# FMC_HPC_LPC_Signals.net
KiCad netlist of a schematic drawn in Altium Designer
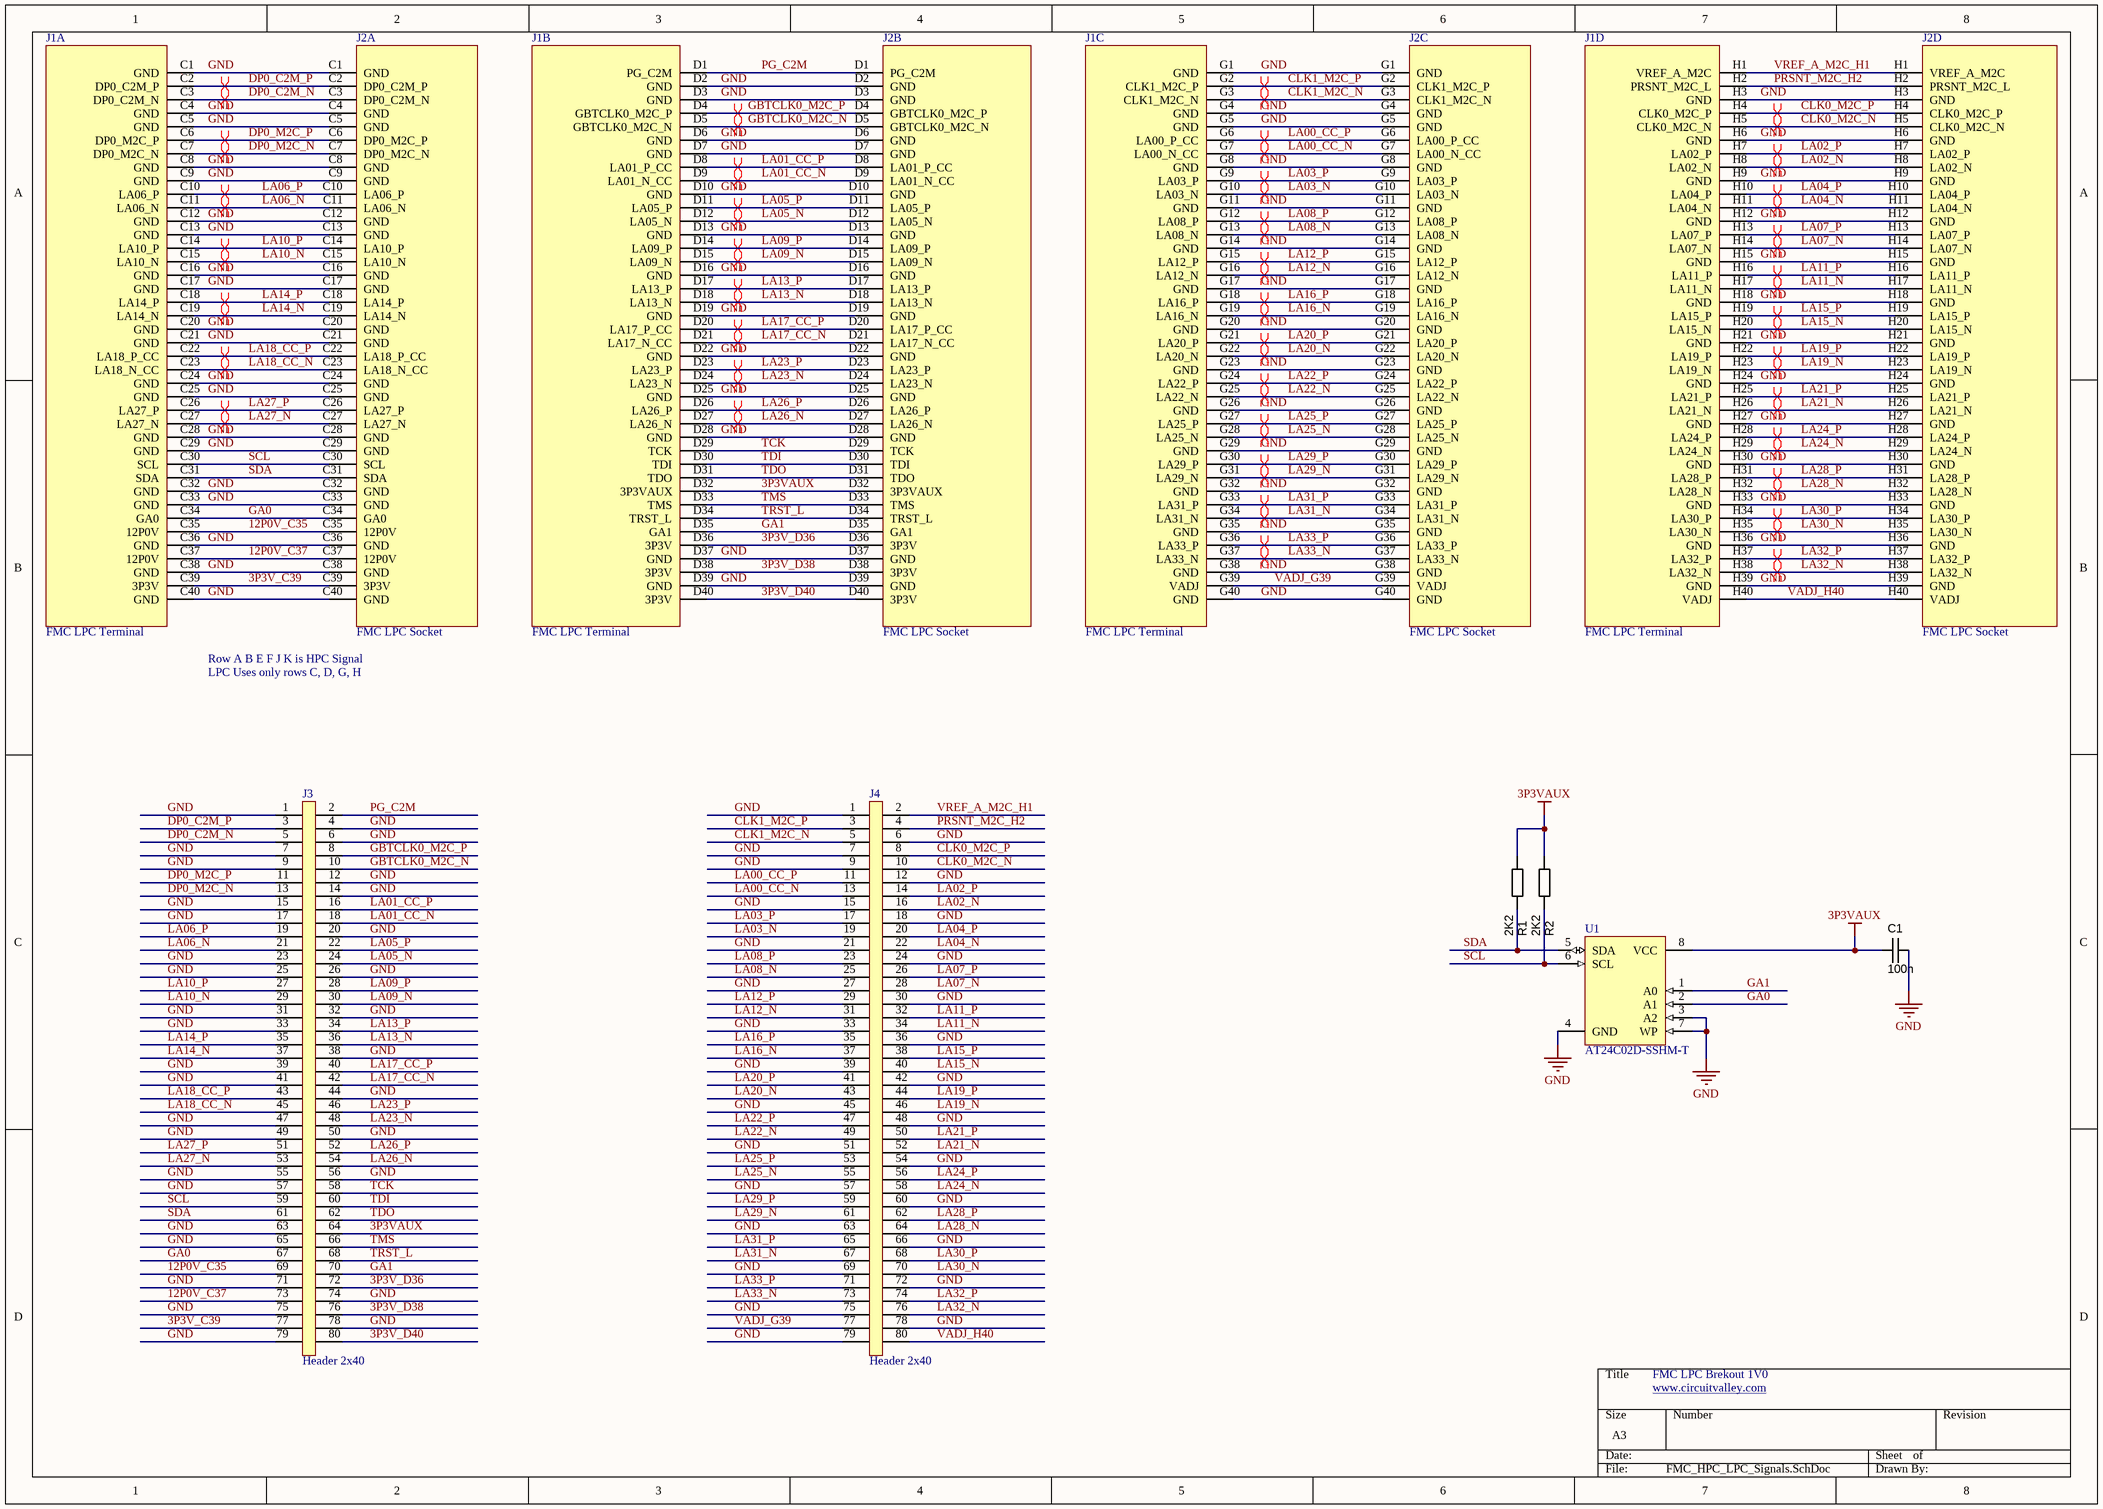
[diagram p0: FMC_HPC_LPC_Signals.SchDoc]

(export (version "E")
  (design (tool "Eeschema 10.0.6"))
  (components
    (comp (ref "C1")
      (value "100n")
      (footprint "CAPC1005N")
      (description "Capacitor SMD Cer 10nF 10% 16V X7R 0402")
      (fields (field (name "TOLERANCE") "±10%"))
      (libsource (lib "PBL - Capacitors") (part "CAPC_10n_0402_16V_10%"))
    )
    (comp (ref "J1")
      (value "FMC LPC Terminal")
      (footprint "SAMTEC_ASP-134604-01")
      (description "FMC LPC Connector Terminal ASP-134604-01")
      (libsource (lib "cvlib") (part "FMC_LPC_TERMINAL"))
    )
    (comp (ref "J2")
      (value "FMC LPC Socket")
      (footprint "SAMTEC_ASP-134603-01")
      (description "FMC LPC Connector Socket  ASP-134603-01")
      (libsource (lib "cvlib") (part "FMC_LPC_SOCKET"))
    )
    (comp (ref "J3")
      (value "Header 2x40")
      (footprint "FTSH-140-01-L-DV")
      (libsource (lib "cvlib") (part "Header_2x40"))
    )
    (comp (ref "J4")
      (value "Header 2x40")
      (footprint "FTSH-140-01-L-DV")
      (libsource (lib "cvlib") (part "Header_2x40"))
    )
    (comp (ref "R1")
      (value "2K2")
      (footprint "RESC1005N")
      (description "Resistor SMD chip 3.3k Ohm 0.063W 5% 0402")
      (fields (field (name "TOLERANCE") "±5%") (field (name "Comment") "Thick Film"))
      (libsource (lib "PBL - Resistors") (part "RES_3K3_0402_5%"))
    )
    (comp (ref "R2")
      (value "2K2")
      (footprint "RESC1005N")
      (description "Resistor SMD chip 3.3k Ohm 0.063W 5% 0402")
      (fields (field (name "TOLERANCE") "±5%") (field (name "Comment") "Thick Film"))
      (libsource (lib "PBL - Resistors") (part "RES_3K3_0402_5%"))
    )
    (comp (ref "U1")
      (value "AT24C02D-SSHM-T")
      (footprint "SOIC8")
      (description "2Kbit I2C EEPROM")
      (libsource (lib "cvlib") (part "AT24C02D-SSHM-T"))
    )
  )
  (nets
    (net (code "1") (name "/3P3V_C39") (class "Default")
      (node (ref "J1") (pin "C39") (pinfunction "3P3V_C39") (pintype "passive"))
      (node (ref "J2") (pin "C39") (pinfunction "3P3V_C39") (pintype "passive"))
      (node (ref "J3") (pin "77") (pinfunction "77_77") (pintype "passive"))
    )
    (net (code "2") (name "/3P3V_D36") (class "Default")
      (node (ref "J1") (pin "D36") (pinfunction "3P3V_D36") (pintype "passive"))
      (node (ref "J2") (pin "D36") (pinfunction "3P3V_D36") (pintype "passive"))
      (node (ref "J3") (pin "72") (pinfunction "72_72") (pintype "passive"))
    )
    (net (code "3") (name "/3P3V_D38") (class "Default")
      (node (ref "J1") (pin "D38") (pinfunction "3P3V_D38") (pintype "passive"))
      (node (ref "J2") (pin "D38") (pinfunction "3P3V_D38") (pintype "passive"))
      (node (ref "J3") (pin "76") (pinfunction "76_76") (pintype "passive"))
    )
    (net (code "4") (name "/3P3V_D40") (class "Default")
      (node (ref "J1") (pin "D40") (pinfunction "3P3V_D40") (pintype "passive"))
      (node (ref "J2") (pin "D40") (pinfunction "3P3V_D40") (pintype "passive"))
      (node (ref "J3") (pin "80") (pinfunction "80_80") (pintype "passive"))
    )
    (net (code "5") (name "/12P0V_C35") (class "Default")
      (node (ref "J1") (pin "C35") (pinfunction "12P0V_C35") (pintype "passive"))
      (node (ref "J2") (pin "C35") (pinfunction "12P0V_C35") (pintype "passive"))
      (node (ref "J3") (pin "69") (pinfunction "69_69") (pintype "passive"))
    )
    (net (code "6") (name "/12P0V_C37") (class "Default")
      (node (ref "J1") (pin "C37") (pinfunction "12P0V_C37") (pintype "passive"))
      (node (ref "J2") (pin "C37") (pinfunction "12P0V_C37") (pintype "passive"))
      (node (ref "J3") (pin "73") (pinfunction "73_73") (pintype "passive"))
    )
    (net (code "7") (name "/CLK0_M2C_N") (class "Default")
      (node (ref "J1") (pin "H5") (pinfunction "CLK0_M2C_N_H5") (pintype "passive"))
      (node (ref "J2") (pin "H5") (pinfunction "CLK0_M2C_N_H5") (pintype "passive"))
      (node (ref "J4") (pin "10") (pinfunction "10_10") (pintype "passive"))
    )
    (net (code "8") (name "/CLK0_M2C_P") (class "Default")
      (node (ref "J1") (pin "H4") (pinfunction "CLK0_M2C_P_H4") (pintype "passive"))
      (node (ref "J2") (pin "H4") (pinfunction "CLK0_M2C_P_H4") (pintype "passive"))
      (node (ref "J4") (pin "8") (pinfunction "8_8") (pintype "passive"))
    )
    (net (code "9") (name "/CLK1_M2C_N") (class "Default")
      (node (ref "J1") (pin "G3") (pinfunction "CLK1_M2C_N_G3") (pintype "passive"))
      (node (ref "J2") (pin "G3") (pinfunction "CLK1_M2C_N_G3") (pintype "passive"))
      (node (ref "J4") (pin "5") (pinfunction "5_5") (pintype "passive"))
    )
    (net (code "10") (name "/CLK1_M2C_P") (class "Default")
      (node (ref "J1") (pin "G2") (pinfunction "CLK1_M2C_P_G2") (pintype "passive"))
      (node (ref "J2") (pin "G2") (pinfunction "CLK1_M2C_P_G2") (pintype "passive"))
      (node (ref "J4") (pin "3") (pinfunction "3_3") (pintype "passive"))
    )
    (net (code "11") (name "/DP0_C2M_N") (class "Default")
      (node (ref "J1") (pin "C3") (pinfunction "DP0_C2M_N_C3") (pintype "passive"))
      (node (ref "J2") (pin "C3") (pinfunction "DP0_C2M_N_C3") (pintype "passive"))
      (node (ref "J3") (pin "5") (pinfunction "5_5") (pintype "passive"))
    )
    (net (code "12") (name "/DP0_C2M_P") (class "Default")
      (node (ref "J1") (pin "C2") (pinfunction "DP0_C2M_P_C2") (pintype "passive"))
      (node (ref "J2") (pin "C2") (pinfunction "DP0_C2M_P_C2") (pintype "passive"))
      (node (ref "J3") (pin "3") (pinfunction "3_3") (pintype "passive"))
    )
    (net (code "13") (name "/DP0_M2C_N") (class "Default")
      (node (ref "J1") (pin "C7") (pinfunction "DP0_M2C_N_C7") (pintype "passive"))
      (node (ref "J2") (pin "C7") (pinfunction "DP0_M2C_N_C7") (pintype "passive"))
      (node (ref "J3") (pin "13") (pinfunction "13_13") (pintype "passive"))
    )
    (net (code "14") (name "/DP0_M2C_P") (class "Default")
      (node (ref "J1") (pin "C6") (pinfunction "DP0_M2C_P_C6") (pintype "passive"))
      (node (ref "J2") (pin "C6") (pinfunction "DP0_M2C_P_C6") (pintype "passive"))
      (node (ref "J3") (pin "11") (pinfunction "11_11") (pintype "passive"))
    )
    (net (code "15") (name "/GA0") (class "Default")
      (node (ref "J1") (pin "C34") (pinfunction "GA0_C34") (pintype "passive"))
      (node (ref "J2") (pin "C34") (pinfunction "GA0_C34") (pintype "passive"))
      (node (ref "J3") (pin "67") (pinfunction "67_67") (pintype "passive"))
      (node (ref "U1") (pin "2") (pinfunction "A1_2") (pintype "input"))
    )
    (net (code "16") (name "/GA1") (class "Default")
      (node (ref "J1") (pin "D35") (pinfunction "GA1_D35") (pintype "passive"))
      (node (ref "J2") (pin "D35") (pinfunction "GA1_D35") (pintype "passive"))
      (node (ref "J3") (pin "70") (pinfunction "70_70") (pintype "passive"))
      (node (ref "U1") (pin "1") (pinfunction "A0_1") (pintype "input"))
    )
    (net (code "17") (name "/GBTCLK0_M2C_N") (class "Default")
      (node (ref "J1") (pin "D5") (pinfunction "GBTCLK0_M2C_N_D5") (pintype "passive"))
      (node (ref "J2") (pin "D5") (pinfunction "GBTCLK0_M2C_N_D5") (pintype "passive"))
      (node (ref "J3") (pin "10") (pinfunction "10_10") (pintype "passive"))
    )
    (net (code "18") (name "/GBTCLK0_M2C_P") (class "Default")
      (node (ref "J1") (pin "D4") (pinfunction "GBTCLK0_M2C_P_D4") (pintype "passive"))
      (node (ref "J2") (pin "D4") (pinfunction "GBTCLK0_M2C_P_D4") (pintype "passive"))
      (node (ref "J3") (pin "8") (pinfunction "8_8") (pintype "passive"))
    )
    (net (code "19") (name "/LA00_CC_N") (class "Default")
      (node (ref "J1") (pin "G7") (pinfunction "LA00_N_CC_G7") (pintype "passive"))
      (node (ref "J2") (pin "G7") (pinfunction "LA00_N_CC_G7") (pintype "passive"))
      (node (ref "J4") (pin "13") (pinfunction "13_13") (pintype "passive"))
    )
    (net (code "20") (name "/LA00_CC_P") (class "Default")
      (node (ref "J1") (pin "G6") (pinfunction "LA00_P_CC_G6") (pintype "passive"))
      (node (ref "J2") (pin "G6") (pinfunction "LA00_P_CC_G6") (pintype "passive"))
      (node (ref "J4") (pin "11") (pinfunction "11_11") (pintype "passive"))
    )
    (net (code "21") (name "/LA01_CC_N") (class "Default")
      (node (ref "J1") (pin "D9") (pinfunction "LA01_N_CC_D9") (pintype "passive"))
      (node (ref "J2") (pin "D9") (pinfunction "LA01_N_CC_D9") (pintype "passive"))
      (node (ref "J3") (pin "18") (pinfunction "18_18") (pintype "passive"))
    )
    (net (code "22") (name "/LA01_CC_P") (class "Default")
      (node (ref "J1") (pin "D8") (pinfunction "LA01_P_CC_D8") (pintype "passive"))
      (node (ref "J2") (pin "D8") (pinfunction "LA01_P_CC_D8") (pintype "passive"))
      (node (ref "J3") (pin "16") (pinfunction "16_16") (pintype "passive"))
    )
    (net (code "23") (name "/LA02_N") (class "Default")
      (node (ref "J1") (pin "H8") (pinfunction "LA02_N_H8") (pintype "passive"))
      (node (ref "J2") (pin "H8") (pinfunction "LA02_N_H8") (pintype "passive"))
      (node (ref "J4") (pin "16") (pinfunction "16_16") (pintype "passive"))
    )
    (net (code "24") (name "/LA02_P") (class "Default")
      (node (ref "J1") (pin "H7") (pinfunction "LA02_P_H7") (pintype "passive"))
      (node (ref "J2") (pin "H7") (pinfunction "LA02_P_H7") (pintype "passive"))
      (node (ref "J4") (pin "14") (pinfunction "14_14") (pintype "passive"))
    )
    (net (code "25") (name "/LA03_N") (class "Default")
      (node (ref "J1") (pin "G10") (pinfunction "LA03_N_G10") (pintype "passive"))
      (node (ref "J2") (pin "G10") (pinfunction "LA03_N_G10") (pintype "passive"))
      (node (ref "J4") (pin "19") (pinfunction "19_19") (pintype "passive"))
    )
    (net (code "26") (name "/LA03_P") (class "Default")
      (node (ref "J1") (pin "G9") (pinfunction "LA03_P_G9") (pintype "passive"))
      (node (ref "J2") (pin "G9") (pinfunction "LA03_P_G9") (pintype "passive"))
      (node (ref "J4") (pin "17") (pinfunction "17_17") (pintype "passive"))
    )
    (net (code "27") (name "/LA04_N") (class "Default")
      (node (ref "J1") (pin "H11") (pinfunction "LA04_N_H11") (pintype "passive"))
      (node (ref "J2") (pin "H11") (pinfunction "LA04_N_H11") (pintype "passive"))
      (node (ref "J4") (pin "22") (pinfunction "22_22") (pintype "passive"))
    )
    (net (code "28") (name "/LA04_P") (class "Default")
      (node (ref "J1") (pin "H10") (pinfunction "LA04_P_H10") (pintype "passive"))
      (node (ref "J2") (pin "H10") (pinfunction "LA04_P_H10") (pintype "passive"))
      (node (ref "J4") (pin "20") (pinfunction "20_20") (pintype "passive"))
    )
    (net (code "29") (name "/LA05_N") (class "Default")
      (node (ref "J1") (pin "D12") (pinfunction "LA05_N_D12") (pintype "passive"))
      (node (ref "J2") (pin "D12") (pinfunction "LA05_N_D12") (pintype "passive"))
      (node (ref "J3") (pin "24") (pinfunction "24_24") (pintype "passive"))
    )
    (net (code "30") (name "/LA05_P") (class "Default")
      (node (ref "J1") (pin "D11") (pinfunction "LA05_P_D11") (pintype "passive"))
      (node (ref "J2") (pin "D11") (pinfunction "LA05_P_D11") (pintype "passive"))
      (node (ref "J3") (pin "22") (pinfunction "22_22") (pintype "passive"))
    )
    (net (code "31") (name "/LA06_N") (class "Default")
      (node (ref "J1") (pin "C11") (pinfunction "LA06_N_C11") (pintype "passive"))
      (node (ref "J2") (pin "C11") (pinfunction "LA06_N_C11") (pintype "passive"))
      (node (ref "J3") (pin "21") (pinfunction "21_21") (pintype "passive"))
    )
    (net (code "32") (name "/LA06_P") (class "Default")
      (node (ref "J1") (pin "C10") (pinfunction "LA06_P_C10") (pintype "passive"))
      (node (ref "J2") (pin "C10") (pinfunction "LA06_P_C10") (pintype "passive"))
      (node (ref "J3") (pin "19") (pinfunction "19_19") (pintype "passive"))
    )
    (net (code "33") (name "/LA07_N") (class "Default")
      (node (ref "J1") (pin "H14") (pinfunction "LA07_N_H14") (pintype "passive"))
      (node (ref "J2") (pin "H14") (pinfunction "LA07_N_H14") (pintype "passive"))
      (node (ref "J4") (pin "28") (pinfunction "28_28") (pintype "passive"))
    )
    (net (code "34") (name "/LA07_P") (class "Default")
      (node (ref "J1") (pin "H13") (pinfunction "LA07_P_H13") (pintype "passive"))
      (node (ref "J2") (pin "H13") (pinfunction "LA07_P_H13") (pintype "passive"))
      (node (ref "J4") (pin "26") (pinfunction "26_26") (pintype "passive"))
    )
    (net (code "35") (name "/LA08_N") (class "Default")
      (node (ref "J1") (pin "G13") (pinfunction "LA08_N_G13") (pintype "passive"))
      (node (ref "J2") (pin "G13") (pinfunction "LA08_N_G13") (pintype "passive"))
      (node (ref "J4") (pin "25") (pinfunction "25_25") (pintype "passive"))
    )
    (net (code "36") (name "/LA08_P") (class "Default")
      (node (ref "J1") (pin "G12") (pinfunction "LA08_P_G12") (pintype "passive"))
      (node (ref "J2") (pin "G12") (pinfunction "LA08_P_G12") (pintype "passive"))
      (node (ref "J4") (pin "23") (pinfunction "23_23") (pintype "passive"))
    )
    (net (code "37") (name "/LA09_N") (class "Default")
      (node (ref "J1") (pin "D15") (pinfunction "LA09_N_D15") (pintype "passive"))
      (node (ref "J2") (pin "D15") (pinfunction "LA09_N_D15") (pintype "passive"))
      (node (ref "J3") (pin "30") (pinfunction "30_30") (pintype "passive"))
    )
    (net (code "38") (name "/LA09_P") (class "Default")
      (node (ref "J1") (pin "D14") (pinfunction "LA09_P_D14") (pintype "passive"))
      (node (ref "J2") (pin "D14") (pinfunction "LA09_P_D14") (pintype "passive"))
      (node (ref "J3") (pin "28") (pinfunction "28_28") (pintype "passive"))
    )
    (net (code "39") (name "/LA10_N") (class "Default")
      (node (ref "J1") (pin "C15") (pinfunction "LA10_N_C15") (pintype "passive"))
      (node (ref "J2") (pin "C15") (pinfunction "LA10_N_C15") (pintype "passive"))
      (node (ref "J3") (pin "29") (pinfunction "29_29") (pintype "passive"))
    )
    (net (code "40") (name "/LA10_P") (class "Default")
      (node (ref "J1") (pin "C14") (pinfunction "LA10_P_C14") (pintype "passive"))
      (node (ref "J2") (pin "C14") (pinfunction "LA10_P_C14") (pintype "passive"))
      (node (ref "J3") (pin "27") (pinfunction "27_27") (pintype "passive"))
    )
    (net (code "41") (name "/LA11_N") (class "Default")
      (node (ref "J1") (pin "H17") (pinfunction "LA11_N_H17") (pintype "passive"))
      (node (ref "J2") (pin "H17") (pinfunction "LA11_N_H17") (pintype "passive"))
      (node (ref "J4") (pin "34") (pinfunction "34_34") (pintype "passive"))
    )
    (net (code "42") (name "/LA11_P") (class "Default")
      (node (ref "J1") (pin "H16") (pinfunction "LA11_P_H16") (pintype "passive"))
      (node (ref "J2") (pin "H16") (pinfunction "LA11_P_H16") (pintype "passive"))
      (node (ref "J4") (pin "32") (pinfunction "32_32") (pintype "passive"))
    )
    (net (code "43") (name "/LA12_N") (class "Default")
      (node (ref "J1") (pin "G16") (pinfunction "LA12_N_G16") (pintype "passive"))
      (node (ref "J2") (pin "G16") (pinfunction "LA12_N_G16") (pintype "passive"))
      (node (ref "J4") (pin "31") (pinfunction "31_31") (pintype "passive"))
    )
    (net (code "44") (name "/LA12_P") (class "Default")
      (node (ref "J1") (pin "G15") (pinfunction "LA12_P_G15") (pintype "passive"))
      (node (ref "J2") (pin "G15") (pinfunction "LA12_P_G15") (pintype "passive"))
      (node (ref "J4") (pin "29") (pinfunction "29_29") (pintype "passive"))
    )
    (net (code "45") (name "/LA13_N") (class "Default")
      (node (ref "J1") (pin "D18") (pinfunction "LA13_N_D18") (pintype "passive"))
      (node (ref "J2") (pin "D18") (pinfunction "LA13_N_D18") (pintype "passive"))
      (node (ref "J3") (pin "36") (pinfunction "36_36") (pintype "passive"))
    )
    (net (code "46") (name "/LA13_P") (class "Default")
      (node (ref "J1") (pin "D17") (pinfunction "LA13_P_D17") (pintype "passive"))
      (node (ref "J2") (pin "D17") (pinfunction "LA13_P_D17") (pintype "passive"))
      (node (ref "J3") (pin "34") (pinfunction "34_34") (pintype "passive"))
    )
    (net (code "47") (name "/LA14_N") (class "Default")
      (node (ref "J1") (pin "C19") (pinfunction "LA14_N_C19") (pintype "passive"))
      (node (ref "J2") (pin "C19") (pinfunction "LA14_N_C19") (pintype "passive"))
      (node (ref "J3") (pin "37") (pinfunction "37_37") (pintype "passive"))
    )
    (net (code "48") (name "/LA14_P") (class "Default")
      (node (ref "J1") (pin "C18") (pinfunction "LA14_P_C18") (pintype "passive"))
      (node (ref "J2") (pin "C18") (pinfunction "LA14_P_C18") (pintype "passive"))
      (node (ref "J3") (pin "35") (pinfunction "35_35") (pintype "passive"))
    )
    (net (code "49") (name "/LA15_N") (class "Default")
      (node (ref "J1") (pin "H20") (pinfunction "LA15_N_H20") (pintype "passive"))
      (node (ref "J2") (pin "H20") (pinfunction "LA15_N_H20") (pintype "passive"))
      (node (ref "J4") (pin "40") (pinfunction "40_40") (pintype "passive"))
    )
    (net (code "50") (name "/LA15_P") (class "Default")
      (node (ref "J1") (pin "H19") (pinfunction "LA15_P_H19") (pintype "passive"))
      (node (ref "J2") (pin "H19") (pinfunction "LA15_P_H19") (pintype "passive"))
      (node (ref "J4") (pin "38") (pinfunction "38_38") (pintype "passive"))
    )
    (net (code "51") (name "/LA16_N") (class "Default")
      (node (ref "J1") (pin "G19") (pinfunction "LA16_N_G19") (pintype "passive"))
      (node (ref "J2") (pin "G19") (pinfunction "LA16_N_G19") (pintype "passive"))
      (node (ref "J4") (pin "37") (pinfunction "37_37") (pintype "passive"))
    )
    (net (code "52") (name "/LA16_P") (class "Default")
      (node (ref "J1") (pin "G18") (pinfunction "LA16_P_G18") (pintype "passive"))
      (node (ref "J2") (pin "G18") (pinfunction "LA16_P_G18") (pintype "passive"))
      (node (ref "J4") (pin "35") (pinfunction "35_35") (pintype "passive"))
    )
    (net (code "53") (name "/LA17_CC_N") (class "Default")
      (node (ref "J1") (pin "D21") (pinfunction "LA17_N_CC_D21") (pintype "passive"))
      (node (ref "J2") (pin "D21") (pinfunction "LA17_N_CC_D21") (pintype "passive"))
      (node (ref "J3") (pin "42") (pinfunction "42_42") (pintype "passive"))
    )
    (net (code "54") (name "/LA17_CC_P") (class "Default")
      (node (ref "J1") (pin "D20") (pinfunction "LA17_P_CC_D20") (pintype "passive"))
      (node (ref "J2") (pin "D20") (pinfunction "LA17_P_CC_D20") (pintype "passive"))
      (node (ref "J3") (pin "40") (pinfunction "40_40") (pintype "passive"))
    )
    (net (code "55") (name "/LA18_CC_N") (class "Default")
      (node (ref "J1") (pin "C23") (pinfunction "LA18_N_CC_C23") (pintype "passive"))
      (node (ref "J2") (pin "C23") (pinfunction "LA18_N_CC_C23") (pintype "passive"))
      (node (ref "J3") (pin "45") (pinfunction "45_45") (pintype "passive"))
    )
    (net (code "56") (name "/LA18_CC_P") (class "Default")
      (node (ref "J1") (pin "C22") (pinfunction "LA18_P_CC_C22") (pintype "passive"))
      (node (ref "J2") (pin "C22") (pinfunction "LA18_P_CC_C22") (pintype "passive"))
      (node (ref "J3") (pin "43") (pinfunction "43_43") (pintype "passive"))
    )
    (net (code "57") (name "/LA19_N") (class "Default")
      (node (ref "J1") (pin "H23") (pinfunction "LA19_N_H23") (pintype "passive"))
      (node (ref "J2") (pin "H23") (pinfunction "LA19_N_H23") (pintype "passive"))
      (node (ref "J4") (pin "46") (pinfunction "46_46") (pintype "passive"))
    )
    (net (code "58") (name "/LA19_P") (class "Default")
      (node (ref "J1") (pin "H22") (pinfunction "LA19_P_H22") (pintype "passive"))
      (node (ref "J2") (pin "H22") (pinfunction "LA19_P_H22") (pintype "passive"))
      (node (ref "J4") (pin "44") (pinfunction "44_44") (pintype "passive"))
    )
    (net (code "59") (name "/LA20_N") (class "Default")
      (node (ref "J1") (pin "G22") (pinfunction "LA20_N_G22") (pintype "passive"))
      (node (ref "J2") (pin "G22") (pinfunction "LA20_N_G22") (pintype "passive"))
      (node (ref "J4") (pin "43") (pinfunction "43_43") (pintype "passive"))
    )
    (net (code "60") (name "/LA20_P") (class "Default")
      (node (ref "J1") (pin "G21") (pinfunction "LA20_P_G21") (pintype "passive"))
      (node (ref "J2") (pin "G21") (pinfunction "LA20_P_G21") (pintype "passive"))
      (node (ref "J4") (pin "41") (pinfunction "41_41") (pintype "passive"))
    )
    (net (code "61") (name "/LA21_N") (class "Default")
      (node (ref "J1") (pin "H26") (pinfunction "LA21_N_H26") (pintype "passive"))
      (node (ref "J2") (pin "H26") (pinfunction "LA21_N_H26") (pintype "passive"))
      (node (ref "J4") (pin "52") (pinfunction "52_52") (pintype "passive"))
    )
    (net (code "62") (name "/LA21_P") (class "Default")
      (node (ref "J1") (pin "H25") (pinfunction "LA21_P_H25") (pintype "passive"))
      (node (ref "J2") (pin "H25") (pinfunction "LA21_P_H25") (pintype "passive"))
      (node (ref "J4") (pin "50") (pinfunction "50_50") (pintype "passive"))
    )
    (net (code "63") (name "/LA22_N") (class "Default")
      (node (ref "J1") (pin "G25") (pinfunction "LA22_N_G25") (pintype "passive"))
      (node (ref "J2") (pin "G25") (pinfunction "LA22_N_G25") (pintype "passive"))
      (node (ref "J4") (pin "49") (pinfunction "49_49") (pintype "passive"))
    )
    (net (code "64") (name "/LA22_P") (class "Default")
      (node (ref "J1") (pin "G24") (pinfunction "LA22_P_G24") (pintype "passive"))
      (node (ref "J2") (pin "G24") (pinfunction "LA22_P_G24") (pintype "passive"))
      (node (ref "J4") (pin "47") (pinfunction "47_47") (pintype "passive"))
    )
    (net (code "65") (name "/LA23_N") (class "Default")
      (node (ref "J1") (pin "D24") (pinfunction "LA23_N_D24") (pintype "passive"))
      (node (ref "J2") (pin "D24") (pinfunction "LA23_N_D24") (pintype "passive"))
      (node (ref "J3") (pin "48") (pinfunction "48_48") (pintype "passive"))
    )
    (net (code "66") (name "/LA23_P") (class "Default")
      (node (ref "J1") (pin "D23") (pinfunction "LA23_P_D23") (pintype "passive"))
      (node (ref "J2") (pin "D23") (pinfunction "LA23_P_D23") (pintype "passive"))
      (node (ref "J3") (pin "46") (pinfunction "46_46") (pintype "passive"))
    )
    (net (code "67") (name "/LA24_N") (class "Default")
      (node (ref "J1") (pin "H29") (pinfunction "LA24_N_H29") (pintype "passive"))
      (node (ref "J2") (pin "H29") (pinfunction "LA24_N_H29") (pintype "passive"))
      (node (ref "J4") (pin "58") (pinfunction "58_58") (pintype "passive"))
    )
    (net (code "68") (name "/LA24_P") (class "Default")
      (node (ref "J1") (pin "H28") (pinfunction "LA24_P_H28") (pintype "passive"))
      (node (ref "J2") (pin "H28") (pinfunction "LA24_P_H28") (pintype "passive"))
      (node (ref "J4") (pin "56") (pinfunction "56_56") (pintype "passive"))
    )
    (net (code "69") (name "/LA25_N") (class "Default")
      (node (ref "J1") (pin "G28") (pinfunction "LA25_N_G28") (pintype "passive"))
      (node (ref "J2") (pin "G28") (pinfunction "LA25_N_G28") (pintype "passive"))
      (node (ref "J4") (pin "55") (pinfunction "55_55") (pintype "passive"))
    )
    (net (code "70") (name "/LA25_P") (class "Default")
      (node (ref "J1") (pin "G27") (pinfunction "LA25_P_G27") (pintype "passive"))
      (node (ref "J2") (pin "G27") (pinfunction "LA25_P_G27") (pintype "passive"))
      (node (ref "J4") (pin "53") (pinfunction "53_53") (pintype "passive"))
    )
    (net (code "71") (name "/LA26_N") (class "Default")
      (node (ref "J1") (pin "D27") (pinfunction "LA26_N_D27") (pintype "passive"))
      (node (ref "J2") (pin "D27") (pinfunction "LA26_N_D27") (pintype "passive"))
      (node (ref "J3") (pin "54") (pinfunction "54_54") (pintype "passive"))
    )
    (net (code "72") (name "/LA26_P") (class "Default")
      (node (ref "J1") (pin "D26") (pinfunction "LA26_P_D26") (pintype "passive"))
      (node (ref "J2") (pin "D26") (pinfunction "LA26_P_D26") (pintype "passive"))
      (node (ref "J3") (pin "52") (pinfunction "52_52") (pintype "passive"))
    )
    (net (code "73") (name "/LA27_N") (class "Default")
      (node (ref "J1") (pin "C27") (pinfunction "LA27_N_C27") (pintype "passive"))
      (node (ref "J2") (pin "C27") (pinfunction "LA27_N_C27") (pintype "passive"))
      (node (ref "J3") (pin "53") (pinfunction "53_53") (pintype "passive"))
    )
    (net (code "74") (name "/LA27_P") (class "Default")
      (node (ref "J1") (pin "C26") (pinfunction "LA27_P_C26") (pintype "passive"))
      (node (ref "J2") (pin "C26") (pinfunction "LA27_P_C26") (pintype "passive"))
      (node (ref "J3") (pin "51") (pinfunction "51_51") (pintype "passive"))
    )
    (net (code "75") (name "/LA28_N") (class "Default")
      (node (ref "J1") (pin "H32") (pinfunction "LA28_N_H32") (pintype "passive"))
      (node (ref "J2") (pin "H32") (pinfunction "LA28_N_H32") (pintype "passive"))
      (node (ref "J4") (pin "64") (pinfunction "64_64") (pintype "passive"))
    )
    (net (code "76") (name "/LA28_P") (class "Default")
      (node (ref "J1") (pin "H31") (pinfunction "LA28_P_H31") (pintype "passive"))
      (node (ref "J2") (pin "H31") (pinfunction "LA28_P_H31") (pintype "passive"))
      (node (ref "J4") (pin "62") (pinfunction "62_62") (pintype "passive"))
    )
    (net (code "77") (name "/LA29_N") (class "Default")
      (node (ref "J1") (pin "G31") (pinfunction "LA29_N_G31") (pintype "passive"))
      (node (ref "J2") (pin "G31") (pinfunction "LA29_N_G31") (pintype "passive"))
      (node (ref "J4") (pin "61") (pinfunction "61_61") (pintype "passive"))
    )
    (net (code "78") (name "/LA29_P") (class "Default")
      (node (ref "J1") (pin "G30") (pinfunction "LA29_P_G30") (pintype "passive"))
      (node (ref "J2") (pin "G30") (pinfunction "LA29_P_G30") (pintype "passive"))
      (node (ref "J4") (pin "59") (pinfunction "59_59") (pintype "passive"))
    )
    (net (code "79") (name "/LA30_N") (class "Default")
      (node (ref "J1") (pin "H35") (pinfunction "LA30_N_H35") (pintype "passive"))
      (node (ref "J2") (pin "H35") (pinfunction "LA30_N_H35") (pintype "passive"))
      (node (ref "J4") (pin "70") (pinfunction "70_70") (pintype "passive"))
    )
    (net (code "80") (name "/LA30_P") (class "Default")
      (node (ref "J1") (pin "H34") (pinfunction "LA30_P_H34") (pintype "passive"))
      (node (ref "J2") (pin "H34") (pinfunction "LA30_P_H34") (pintype "passive"))
      (node (ref "J4") (pin "68") (pinfunction "68_68") (pintype "passive"))
    )
    (net (code "81") (name "/LA31_N") (class "Default")
      (node (ref "J1") (pin "G34") (pinfunction "LA31_N_G34") (pintype "passive"))
      (node (ref "J2") (pin "G34") (pinfunction "LA31_N_G34") (pintype "passive"))
      (node (ref "J4") (pin "67") (pinfunction "67_67") (pintype "passive"))
    )
    (net (code "82") (name "/LA31_P") (class "Default")
      (node (ref "J1") (pin "G33") (pinfunction "LA31_P_G33") (pintype "passive"))
      (node (ref "J2") (pin "G33") (pinfunction "LA31_P_G33") (pintype "passive"))
      (node (ref "J4") (pin "65") (pinfunction "65_65") (pintype "passive"))
    )
    (net (code "83") (name "/LA32_N") (class "Default")
      (node (ref "J1") (pin "H38") (pinfunction "LA32_N_H38") (pintype "passive"))
      (node (ref "J2") (pin "H38") (pinfunction "LA32_N_H38") (pintype "passive"))
      (node (ref "J4") (pin "76") (pinfunction "76_76") (pintype "passive"))
    )
    (net (code "84") (name "/LA32_P") (class "Default")
      (node (ref "J1") (pin "H37") (pinfunction "LA32_P_H37") (pintype "passive"))
      (node (ref "J2") (pin "H37") (pinfunction "LA32_P_H37") (pintype "passive"))
      (node (ref "J4") (pin "74") (pinfunction "74_74") (pintype "passive"))
    )
    (net (code "85") (name "/LA33_N") (class "Default")
      (node (ref "J1") (pin "G37") (pinfunction "LA33_N_G37") (pintype "passive"))
      (node (ref "J2") (pin "G37") (pinfunction "LA33_N_G37") (pintype "passive"))
      (node (ref "J4") (pin "73") (pinfunction "73_73") (pintype "passive"))
    )
    (net (code "86") (name "/LA33_P") (class "Default")
      (node (ref "J1") (pin "G36") (pinfunction "LA33_P_G36") (pintype "passive"))
      (node (ref "J2") (pin "G36") (pinfunction "LA33_P_G36") (pintype "passive"))
      (node (ref "J4") (pin "71") (pinfunction "71_71") (pintype "passive"))
    )
    (net (code "87") (name "/PG_C2M") (class "Default")
      (node (ref "J1") (pin "D1") (pinfunction "PG_C2M_D1") (pintype "passive"))
      (node (ref "J2") (pin "D1") (pinfunction "PG_C2M_D1") (pintype "passive"))
      (node (ref "J3") (pin "2") (pinfunction "2_2") (pintype "passive"))
    )
    (net (code "88") (name "/PRSNT_M2C_H2") (class "Default")
      (node (ref "J1") (pin "H2") (pinfunction "PRSNT_M2C_L_H2") (pintype "passive"))
      (node (ref "J2") (pin "H2") (pinfunction "PRSNT_M2C_L_H2") (pintype "passive"))
      (node (ref "J4") (pin "4") (pinfunction "4_4") (pintype "passive"))
    )
    (net (code "89") (name "/SCL") (class "Default")
      (node (ref "J1") (pin "C30") (pinfunction "SCL_C30") (pintype "passive"))
      (node (ref "J2") (pin "C30") (pinfunction "SCL_C30") (pintype "passive"))
      (node (ref "J3") (pin "59") (pinfunction "59_59") (pintype "passive"))
      (node (ref "R2") (pin "2") (pinfunction "2_2") (pintype "passive"))
      (node (ref "U1") (pin "6") (pinfunction "SCL_6") (pintype "input"))
    )
    (net (code "90") (name "/SDA") (class "Default")
      (node (ref "J1") (pin "C31") (pinfunction "SDA_C31") (pintype "passive"))
      (node (ref "J2") (pin "C31") (pinfunction "SDA_C31") (pintype "passive"))
      (node (ref "J3") (pin "61") (pinfunction "61_61") (pintype "passive"))
      (node (ref "R1") (pin "2") (pinfunction "2_2") (pintype "passive"))
      (node (ref "U1") (pin "5") (pinfunction "SDA_5") (pintype "bidirectional"))
    )
    (net (code "91") (name "/TCK") (class "Default")
      (node (ref "J1") (pin "D29") (pinfunction "TCK_D29") (pintype "passive"))
      (node (ref "J2") (pin "D29") (pinfunction "TCK_D29") (pintype "passive"))
      (node (ref "J3") (pin "58") (pinfunction "58_58") (pintype "passive"))
    )
    (net (code "92") (name "/TDI") (class "Default")
      (node (ref "J1") (pin "D30") (pinfunction "TDI_D30") (pintype "passive"))
      (node (ref "J2") (pin "D30") (pinfunction "TDI_D30") (pintype "passive"))
      (node (ref "J3") (pin "60") (pinfunction "60_60") (pintype "passive"))
    )
    (net (code "93") (name "/TDO") (class "Default")
      (node (ref "J1") (pin "D31") (pinfunction "TDO_D31") (pintype "passive"))
      (node (ref "J2") (pin "D31") (pinfunction "TDO_D31") (pintype "passive"))
      (node (ref "J3") (pin "62") (pinfunction "62_62") (pintype "passive"))
    )
    (net (code "94") (name "/TMS") (class "Default")
      (node (ref "J1") (pin "D33") (pinfunction "TMS_D33") (pintype "passive"))
      (node (ref "J2") (pin "D33") (pinfunction "TMS_D33") (pintype "passive"))
      (node (ref "J3") (pin "66") (pinfunction "66_66") (pintype "passive"))
    )
    (net (code "95") (name "/TRST_L") (class "Default")
      (node (ref "J1") (pin "D34") (pinfunction "TRST_L_D34") (pintype "passive"))
      (node (ref "J2") (pin "D34") (pinfunction "TRST_L_D34") (pintype "passive"))
      (node (ref "J3") (pin "68") (pinfunction "68_68") (pintype "passive"))
    )
    (net (code "96") (name "/VADJ_G39") (class "Default")
      (node (ref "J1") (pin "G39") (pinfunction "VADJ_G39") (pintype "passive"))
      (node (ref "J2") (pin "G39") (pinfunction "VADJ_G39") (pintype "passive"))
      (node (ref "J4") (pin "77") (pinfunction "77_77") (pintype "passive"))
    )
    (net (code "97") (name "/VADJ_H40") (class "Default")
      (node (ref "J1") (pin "H40") (pinfunction "VADJ_H40") (pintype "passive"))
      (node (ref "J2") (pin "H40") (pinfunction "VADJ_H40") (pintype "passive"))
      (node (ref "J4") (pin "80") (pinfunction "80_80") (pintype "passive"))
    )
    (net (code "98") (name "/VREF_A_M2C_H1") (class "Default")
      (node (ref "J1") (pin "H1") (pinfunction "VREF_A_M2C_H1") (pintype "passive"))
      (node (ref "J2") (pin "H1") (pinfunction "VREF_A_M2C_H1") (pintype "passive"))
      (node (ref "J4") (pin "2") (pinfunction "2_2") (pintype "passive"))
    )
    (net (code "99") (name "3P3VAUX") (class "Default")
      (node (ref "C1") (pin "2") (pintype "passive"))
      (node (ref "J1") (pin "D32") (pinfunction "3P3VAUX_D32") (pintype "passive"))
      (node (ref "J2") (pin "D32") (pinfunction "3P3VAUX_D32") (pintype "passive"))
      (node (ref "J3") (pin "64") (pinfunction "64_64") (pintype "passive"))
      (node (ref "R1") (pin "1") (pinfunction "1_1") (pintype "passive"))
      (node (ref "R2") (pin "1") (pinfunction "1_1") (pintype "passive"))
      (node (ref "U1") (pin "8") (pinfunction "VCC_8") (pintype "power_in"))
    )
    (net (code "100") (name "GND") (class "Default")
      (node (ref "C1") (pin "1") (pintype "passive"))
      (node (ref "J1") (pin "C1") (pinfunction "GND_C1") (pintype "passive"))
      (node (ref "J1") (pin "C12") (pinfunction "GND_C12") (pintype "passive"))
      (node (ref "J1") (pin "C13") (pinfunction "GND_C13") (pintype "passive"))
      (node (ref "J1") (pin "C16") (pinfunction "GND_C16") (pintype "passive"))
      (node (ref "J1") (pin "C17") (pinfunction "GND_C17") (pintype "passive"))
      (node (ref "J1") (pin "C20") (pinfunction "GND_C20") (pintype "passive"))
      (node (ref "J1") (pin "C21") (pinfunction "GND_C21") (pintype "passive"))
      (node (ref "J1") (pin "C24") (pinfunction "GND_C24") (pintype "passive"))
      (node (ref "J1") (pin "C25") (pinfunction "GND_C25") (pintype "passive"))
      (node (ref "J1") (pin "C28") (pinfunction "GND_C28") (pintype "passive"))
      (node (ref "J1") (pin "C29") (pinfunction "GND_C29") (pintype "passive"))
      (node (ref "J1") (pin "C32") (pinfunction "GND_C32") (pintype "passive"))
      (node (ref "J1") (pin "C33") (pinfunction "GND_C33") (pintype "passive"))
      (node (ref "J1") (pin "C36") (pinfunction "GND_C36") (pintype "passive"))
      (node (ref "J1") (pin "C38") (pinfunction "GND_C38") (pintype "passive"))
      (node (ref "J1") (pin "C4") (pinfunction "GND_C4") (pintype "passive"))
      (node (ref "J1") (pin "C40") (pinfunction "GND_C40") (pintype "passive"))
      (node (ref "J1") (pin "C5") (pinfunction "GND_C5") (pintype "passive"))
      (node (ref "J1") (pin "C8") (pinfunction "GND_C8") (pintype "passive"))
      (node (ref "J1") (pin "C9") (pinfunction "GND_C9") (pintype "passive"))
      (node (ref "J1") (pin "D10") (pinfunction "GND_D10") (pintype "passive"))
      (node (ref "J1") (pin "D13") (pinfunction "GND_D13") (pintype "passive"))
      (node (ref "J1") (pin "D16") (pinfunction "GND_D16") (pintype "passive"))
      (node (ref "J1") (pin "D19") (pinfunction "GND_D19") (pintype "passive"))
      (node (ref "J1") (pin "D2") (pinfunction "GND_D2") (pintype "passive"))
      (node (ref "J1") (pin "D22") (pinfunction "GND_D22") (pintype "passive"))
      (node (ref "J1") (pin "D25") (pinfunction "GND_D25") (pintype "passive"))
      (node (ref "J1") (pin "D28") (pinfunction "GND_D28") (pintype "passive"))
      (node (ref "J1") (pin "D3") (pinfunction "GND_D3") (pintype "passive"))
      (node (ref "J1") (pin "D37") (pinfunction "GND_D37") (pintype "passive"))
      (node (ref "J1") (pin "D39") (pinfunction "GND_D39") (pintype "passive"))
      (node (ref "J1") (pin "D6") (pinfunction "GND_D6") (pintype "passive"))
      (node (ref "J1") (pin "D7") (pinfunction "GND_D7") (pintype "passive"))
      (node (ref "J1") (pin "G1") (pinfunction "GND_G1") (pintype "passive"))
      (node (ref "J1") (pin "G11") (pinfunction "GND_G11") (pintype "passive"))
      (node (ref "J1") (pin "G14") (pinfunction "GND_G14") (pintype "passive"))
      (node (ref "J1") (pin "G17") (pinfunction "GND_G17") (pintype "passive"))
      (node (ref "J1") (pin "G20") (pinfunction "GND_G20") (pintype "passive"))
      (node (ref "J1") (pin "G23") (pinfunction "GND_G23") (pintype "passive"))
      (node (ref "J1") (pin "G26") (pinfunction "GND_G26") (pintype "passive"))
      (node (ref "J1") (pin "G29") (pinfunction "GND_G29") (pintype "passive"))
      (node (ref "J1") (pin "G32") (pinfunction "GND_G32") (pintype "passive"))
      (node (ref "J1") (pin "G35") (pinfunction "GND_G35") (pintype "passive"))
      (node (ref "J1") (pin "G38") (pinfunction "GND_G38") (pintype "passive"))
      (node (ref "J1") (pin "G4") (pinfunction "GND_G4") (pintype "passive"))
      (node (ref "J1") (pin "G40") (pinfunction "GND_G40") (pintype "passive"))
      (node (ref "J1") (pin "G5") (pinfunction "GND_G5") (pintype "passive"))
      (node (ref "J1") (pin "G8") (pinfunction "GND_G8") (pintype "passive"))
      (node (ref "J1") (pin "H12") (pinfunction "GND_H12") (pintype "passive"))
      (node (ref "J1") (pin "H15") (pinfunction "GND_H15") (pintype "passive"))
      (node (ref "J1") (pin "H18") (pinfunction "GND_H18") (pintype "passive"))
      (node (ref "J1") (pin "H21") (pinfunction "GND_H21") (pintype "passive"))
      (node (ref "J1") (pin "H24") (pinfunction "GND_H24") (pintype "passive"))
      (node (ref "J1") (pin "H27") (pinfunction "GND_H27") (pintype "passive"))
      (node (ref "J1") (pin "H3") (pinfunction "GND_H3") (pintype "passive"))
      (node (ref "J1") (pin "H30") (pinfunction "GND_H30") (pintype "passive"))
      (node (ref "J1") (pin "H33") (pinfunction "GND_H33") (pintype "passive"))
      (node (ref "J1") (pin "H36") (pinfunction "GND_H36") (pintype "passive"))
      (node (ref "J1") (pin "H39") (pinfunction "GND_H39") (pintype "passive"))
      (node (ref "J1") (pin "H6") (pinfunction "GND_H6") (pintype "passive"))
      (node (ref "J1") (pin "H9") (pinfunction "GND_H9") (pintype "passive"))
      (node (ref "J2") (pin "C1") (pinfunction "GND_C1") (pintype "passive"))
      (node (ref "J2") (pin "C12") (pinfunction "GND_C12") (pintype "passive"))
      (node (ref "J2") (pin "C13") (pinfunction "GND_C13") (pintype "passive"))
      (node (ref "J2") (pin "C16") (pinfunction "GND_C16") (pintype "passive"))
      (node (ref "J2") (pin "C17") (pinfunction "GND_C17") (pintype "passive"))
      (node (ref "J2") (pin "C20") (pinfunction "GND_C20") (pintype "passive"))
      (node (ref "J2") (pin "C21") (pinfunction "GND_C21") (pintype "passive"))
      (node (ref "J2") (pin "C24") (pinfunction "GND_C24") (pintype "passive"))
      (node (ref "J2") (pin "C25") (pinfunction "GND_C25") (pintype "passive"))
      (node (ref "J2") (pin "C28") (pinfunction "GND_C28") (pintype "passive"))
      (node (ref "J2") (pin "C29") (pinfunction "GND_C29") (pintype "passive"))
      (node (ref "J2") (pin "C32") (pinfunction "GND_C32") (pintype "passive"))
      (node (ref "J2") (pin "C33") (pinfunction "GND_C33") (pintype "passive"))
      (node (ref "J2") (pin "C36") (pinfunction "GND_C36") (pintype "passive"))
      (node (ref "J2") (pin "C38") (pinfunction "GND_C38") (pintype "passive"))
      (node (ref "J2") (pin "C4") (pinfunction "GND_C4") (pintype "passive"))
      (node (ref "J2") (pin "C40") (pinfunction "GND_C40") (pintype "passive"))
      (node (ref "J2") (pin "C5") (pinfunction "GND_C5") (pintype "passive"))
      (node (ref "J2") (pin "C8") (pinfunction "GND_C8") (pintype "passive"))
      (node (ref "J2") (pin "C9") (pinfunction "GND_C9") (pintype "passive"))
      (node (ref "J2") (pin "D10") (pinfunction "GND_D10") (pintype "passive"))
      (node (ref "J2") (pin "D13") (pinfunction "GND_D13") (pintype "passive"))
      (node (ref "J2") (pin "D16") (pinfunction "GND_D16") (pintype "passive"))
      (node (ref "J2") (pin "D19") (pinfunction "GND_D19") (pintype "passive"))
      (node (ref "J2") (pin "D2") (pinfunction "GND_D2") (pintype "passive"))
      (node (ref "J2") (pin "D22") (pinfunction "GND_D22") (pintype "passive"))
      (node (ref "J2") (pin "D25") (pinfunction "GND_D25") (pintype "passive"))
      (node (ref "J2") (pin "D28") (pinfunction "GND_D28") (pintype "passive"))
      (node (ref "J2") (pin "D3") (pinfunction "GND_D3") (pintype "passive"))
      (node (ref "J2") (pin "D37") (pinfunction "GND_D37") (pintype "passive"))
      (node (ref "J2") (pin "D39") (pinfunction "GND_D39") (pintype "passive"))
      (node (ref "J2") (pin "D6") (pinfunction "GND_D6") (pintype "passive"))
      (node (ref "J2") (pin "D7") (pinfunction "GND_D7") (pintype "passive"))
      (node (ref "J2") (pin "G1") (pinfunction "GND_G1") (pintype "passive"))
      (node (ref "J2") (pin "G11") (pinfunction "GND_G11") (pintype "passive"))
      (node (ref "J2") (pin "G14") (pinfunction "GND_G14") (pintype "passive"))
      (node (ref "J2") (pin "G17") (pinfunction "GND_G17") (pintype "passive"))
      (node (ref "J2") (pin "G20") (pinfunction "GND_G20") (pintype "passive"))
      (node (ref "J2") (pin "G23") (pinfunction "GND_G23") (pintype "passive"))
      (node (ref "J2") (pin "G26") (pinfunction "GND_G26") (pintype "passive"))
      (node (ref "J2") (pin "G29") (pinfunction "GND_G29") (pintype "passive"))
      (node (ref "J2") (pin "G32") (pinfunction "GND_G32") (pintype "passive"))
      (node (ref "J2") (pin "G35") (pinfunction "GND_G35") (pintype "passive"))
      (node (ref "J2") (pin "G38") (pinfunction "GND_G38") (pintype "passive"))
      (node (ref "J2") (pin "G4") (pinfunction "GND_G4") (pintype "passive"))
      (node (ref "J2") (pin "G40") (pinfunction "GND_G40") (pintype "passive"))
      (node (ref "J2") (pin "G5") (pinfunction "GND_G5") (pintype "passive"))
      (node (ref "J2") (pin "G8") (pinfunction "GND_G8") (pintype "passive"))
      (node (ref "J2") (pin "H12") (pinfunction "GND_H12") (pintype "passive"))
      (node (ref "J2") (pin "H15") (pinfunction "GND_H15") (pintype "passive"))
      (node (ref "J2") (pin "H18") (pinfunction "GND_H18") (pintype "passive"))
      (node (ref "J2") (pin "H21") (pinfunction "GND_H21") (pintype "passive"))
      (node (ref "J2") (pin "H24") (pinfunction "GND_H24") (pintype "passive"))
      (node (ref "J2") (pin "H27") (pinfunction "GND_H27") (pintype "passive"))
      (node (ref "J2") (pin "H3") (pinfunction "GND_H3") (pintype "passive"))
      (node (ref "J2") (pin "H30") (pinfunction "GND_H30") (pintype "passive"))
      (node (ref "J2") (pin "H33") (pinfunction "GND_H33") (pintype "passive"))
      (node (ref "J2") (pin "H36") (pinfunction "GND_H36") (pintype "passive"))
      (node (ref "J2") (pin "H39") (pinfunction "GND_H39") (pintype "passive"))
      (node (ref "J2") (pin "H6") (pinfunction "GND_H6") (pintype "passive"))
      (node (ref "J2") (pin "H9") (pinfunction "GND_H9") (pintype "passive"))
      (node (ref "J3") (pin "1") (pinfunction "1_1") (pintype "passive"))
      (node (ref "J3") (pin "12") (pinfunction "12_12") (pintype "passive"))
      (node (ref "J3") (pin "14") (pinfunction "14_14") (pintype "passive"))
      (node (ref "J3") (pin "15") (pinfunction "15_15") (pintype "passive"))
      (node (ref "J3") (pin "17") (pinfunction "17_17") (pintype "passive"))
      (node (ref "J3") (pin "20") (pinfunction "20_20") (pintype "passive"))
      (node (ref "J3") (pin "23") (pinfunction "23_23") (pintype "passive"))
      (node (ref "J3") (pin "25") (pinfunction "25_25") (pintype "passive"))
      (node (ref "J3") (pin "26") (pinfunction "26_26") (pintype "passive"))
      (node (ref "J3") (pin "31") (pinfunction "31_31") (pintype "passive"))
      (node (ref "J3") (pin "32") (pinfunction "32_32") (pintype "passive"))
      (node (ref "J3") (pin "33") (pinfunction "33_33") (pintype "passive"))
      (node (ref "J3") (pin "38") (pinfunction "38_38") (pintype "passive"))
      (node (ref "J3") (pin "39") (pinfunction "39_39") (pintype "passive"))
      (node (ref "J3") (pin "4") (pinfunction "4_4") (pintype "passive"))
      (node (ref "J3") (pin "41") (pinfunction "41_41") (pintype "passive"))
      (node (ref "J3") (pin "44") (pinfunction "44_44") (pintype "passive"))
      (node (ref "J3") (pin "47") (pinfunction "47_47") (pintype "passive"))
      (node (ref "J3") (pin "49") (pinfunction "49_49") (pintype "passive"))
      (node (ref "J3") (pin "50") (pinfunction "50_50") (pintype "passive"))
      (node (ref "J3") (pin "55") (pinfunction "55_55") (pintype "passive"))
      (node (ref "J3") (pin "56") (pinfunction "56_56") (pintype "passive"))
      (node (ref "J3") (pin "57") (pinfunction "57_57") (pintype "passive"))
      (node (ref "J3") (pin "6") (pinfunction "6_6") (pintype "passive"))
      (node (ref "J3") (pin "63") (pinfunction "63_63") (pintype "passive"))
      (node (ref "J3") (pin "65") (pinfunction "65_65") (pintype "passive"))
      (node (ref "J3") (pin "7") (pinfunction "7_7") (pintype "passive"))
      (node (ref "J3") (pin "71") (pinfunction "71_71") (pintype "passive"))
      (node (ref "J3") (pin "74") (pinfunction "74_74") (pintype "passive"))
      (node (ref "J3") (pin "75") (pinfunction "75_75") (pintype "passive"))
      (node (ref "J3") (pin "78") (pinfunction "78_78") (pintype "passive"))
      (node (ref "J3") (pin "79") (pinfunction "79_79") (pintype "passive"))
      (node (ref "J3") (pin "9") (pinfunction "9_9") (pintype "passive"))
      (node (ref "J4") (pin "1") (pinfunction "1_1") (pintype "passive"))
      (node (ref "J4") (pin "12") (pinfunction "12_12") (pintype "passive"))
      (node (ref "J4") (pin "15") (pinfunction "15_15") (pintype "passive"))
      (node (ref "J4") (pin "18") (pinfunction "18_18") (pintype "passive"))
      (node (ref "J4") (pin "21") (pinfunction "21_21") (pintype "passive"))
      (node (ref "J4") (pin "24") (pinfunction "24_24") (pintype "passive"))
      (node (ref "J4") (pin "27") (pinfunction "27_27") (pintype "passive"))
      (node (ref "J4") (pin "30") (pinfunction "30_30") (pintype "passive"))
      (node (ref "J4") (pin "33") (pinfunction "33_33") (pintype "passive"))
      (node (ref "J4") (pin "36") (pinfunction "36_36") (pintype "passive"))
      (node (ref "J4") (pin "39") (pinfunction "39_39") (pintype "passive"))
      (node (ref "J4") (pin "42") (pinfunction "42_42") (pintype "passive"))
      (node (ref "J4") (pin "45") (pinfunction "45_45") (pintype "passive"))
      (node (ref "J4") (pin "48") (pinfunction "48_48") (pintype "passive"))
      (node (ref "J4") (pin "51") (pinfunction "51_51") (pintype "passive"))
      (node (ref "J4") (pin "54") (pinfunction "54_54") (pintype "passive"))
      (node (ref "J4") (pin "57") (pinfunction "57_57") (pintype "passive"))
      (node (ref "J4") (pin "6") (pinfunction "6_6") (pintype "passive"))
      (node (ref "J4") (pin "60") (pinfunction "60_60") (pintype "passive"))
      (node (ref "J4") (pin "63") (pinfunction "63_63") (pintype "passive"))
      (node (ref "J4") (pin "66") (pinfunction "66_66") (pintype "passive"))
      (node (ref "J4") (pin "69") (pinfunction "69_69") (pintype "passive"))
      (node (ref "J4") (pin "7") (pinfunction "7_7") (pintype "passive"))
      (node (ref "J4") (pin "72") (pinfunction "72_72") (pintype "passive"))
      (node (ref "J4") (pin "75") (pinfunction "75_75") (pintype "passive"))
      (node (ref "J4") (pin "78") (pinfunction "78_78") (pintype "passive"))
      (node (ref "J4") (pin "79") (pinfunction "79_79") (pintype "passive"))
      (node (ref "J4") (pin "9") (pinfunction "9_9") (pintype "passive"))
      (node (ref "U1") (pin "3") (pinfunction "A2_3") (pintype "input"))
      (node (ref "U1") (pin "4") (pinfunction "GND_4") (pintype "power_in"))
      (node (ref "U1") (pin "7") (pinfunction "WP_7") (pintype "input"))
    )
  )
)
